# MUX_EEM_EXT.net
KiCad netlist of a schematic drawn in Altium Designer
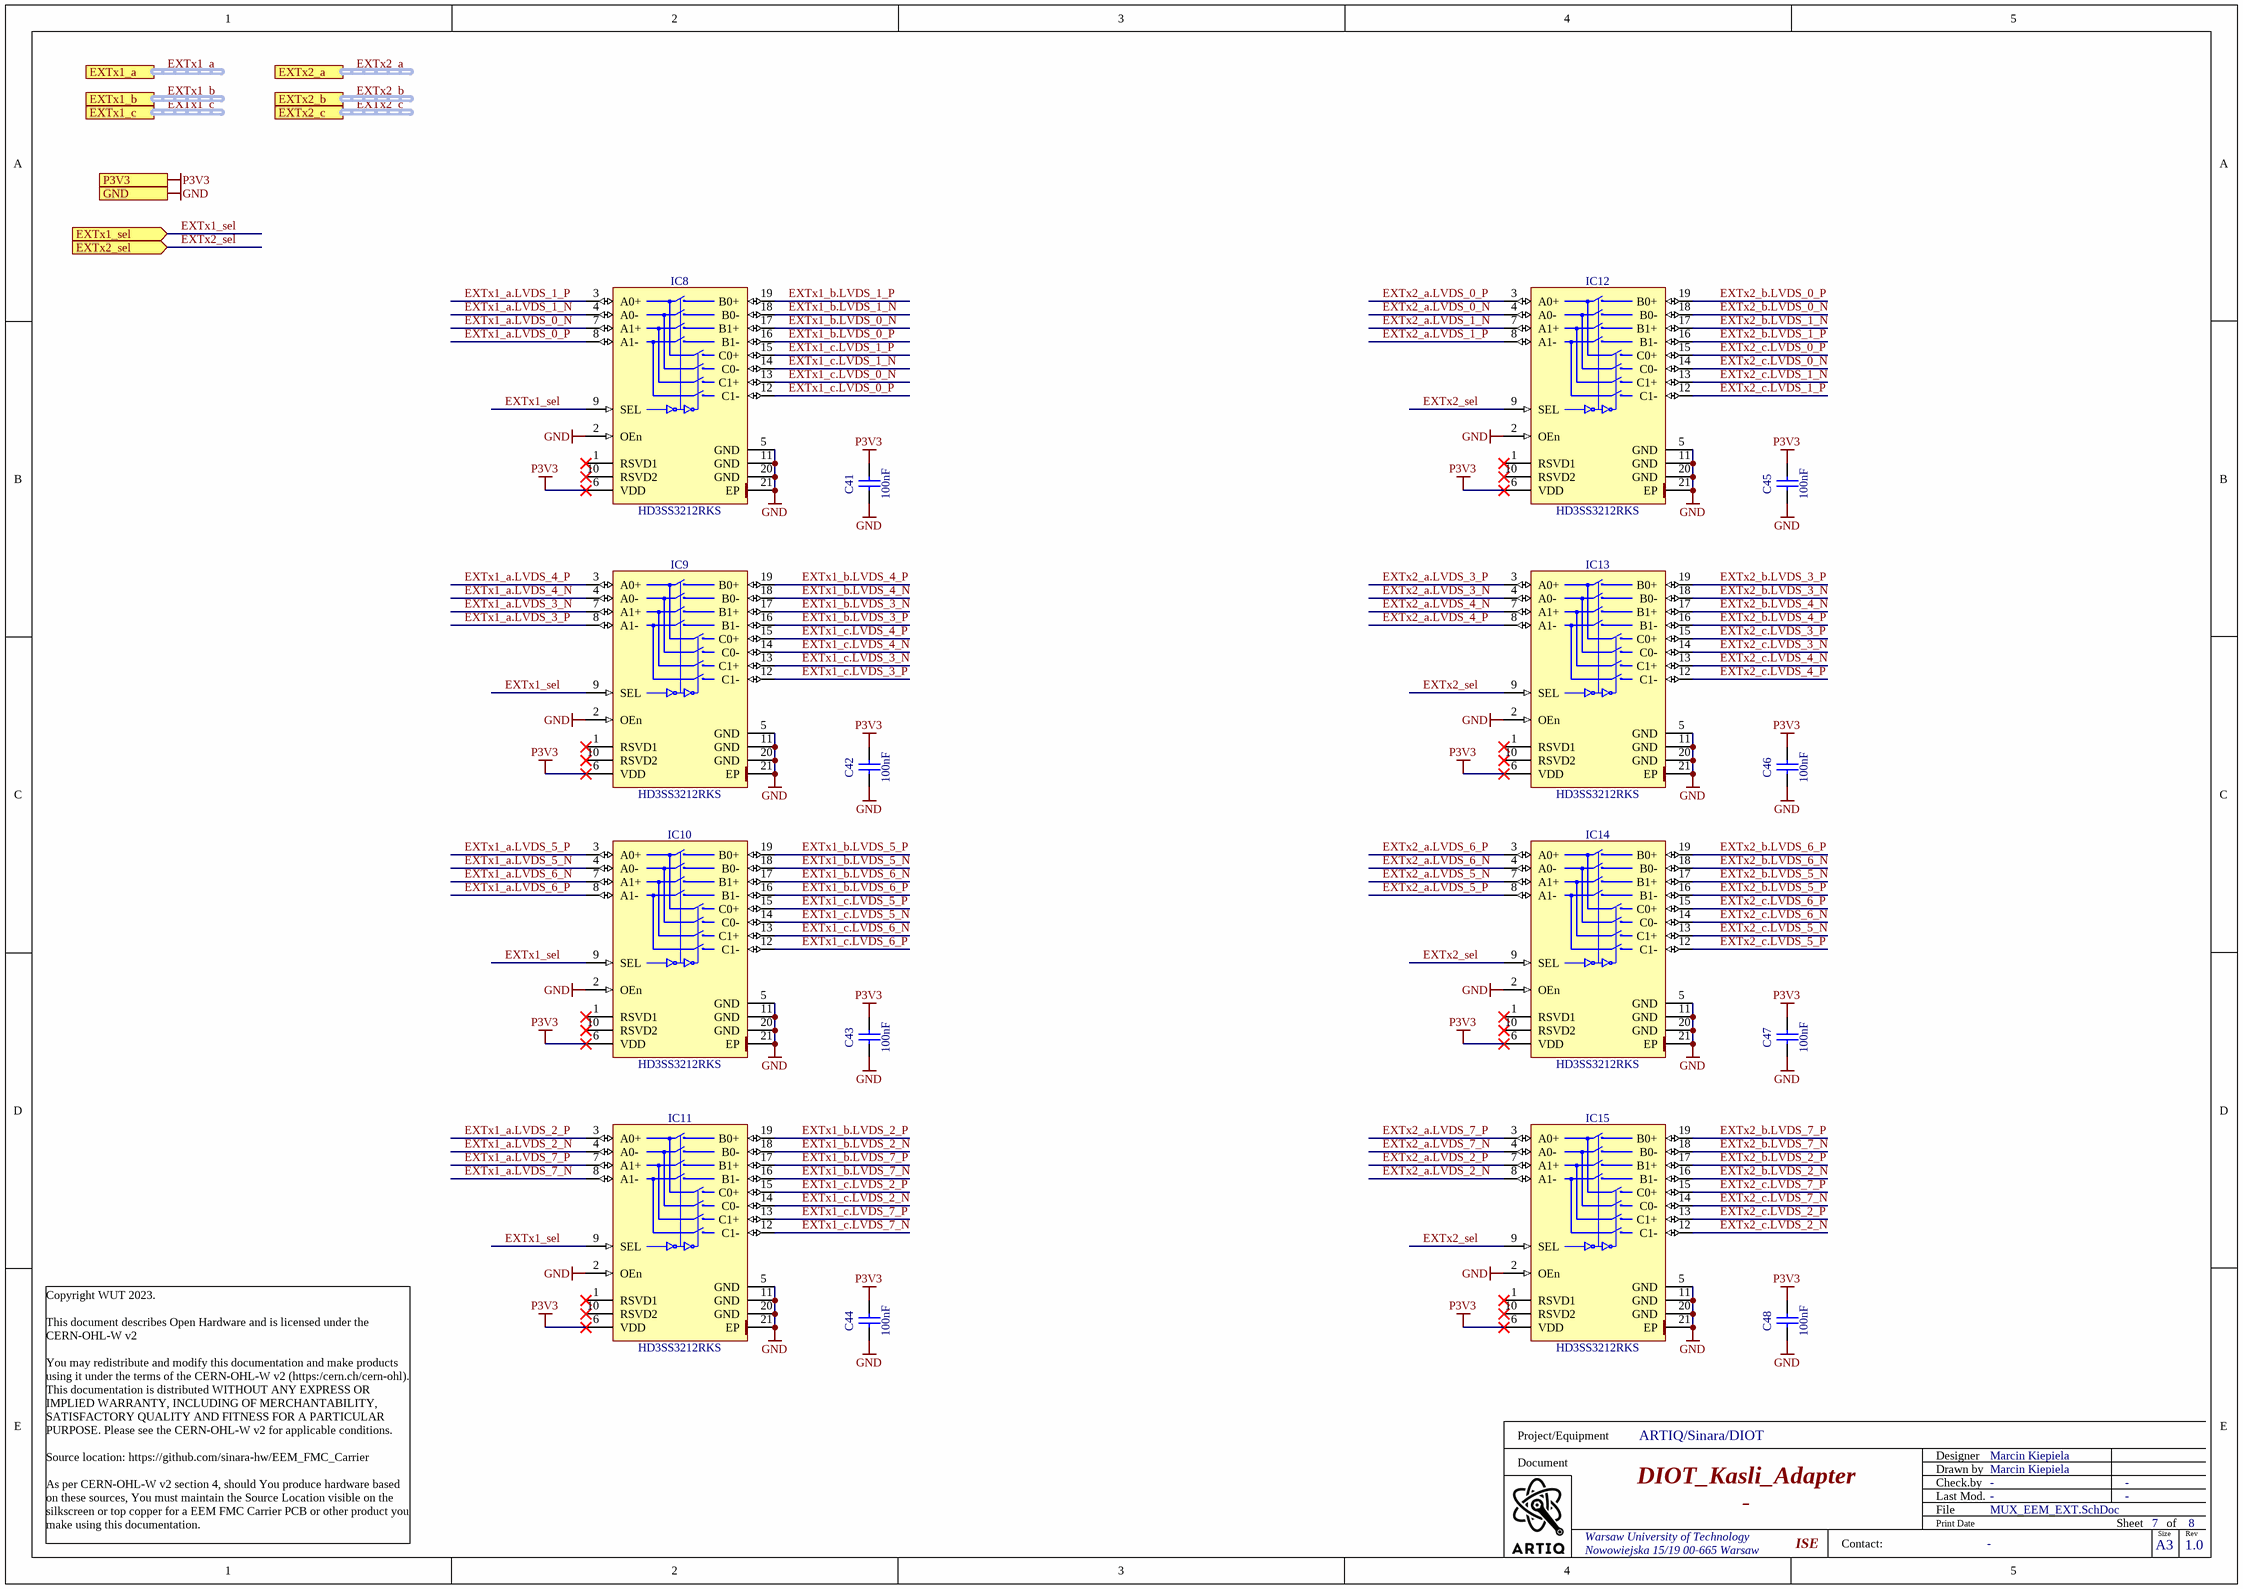
[diagram p0: MUX_EEM_EXT.SchDoc]

(export (version "E")
  (design (tool "Eeschema 10.0.6"))
  (components
    (comp (ref "C41")
      (value "100nF")
      (footprint "CAPC1005X55N")
      (description "Non-polarised capacitor")
      (fields
        (field (name "PART NUMBER") "CC0402_100NF_16V_10%_X7R")
        (field (name "VOLTAGE") "16V")
        (field (name "AUTHOR") "CERN DEM JLC")
      )
      (libsource (lib "Capacitors") (part "Capacitor - non polarized"))
    )
    (comp (ref "C42")
      (value "100nF")
      (footprint "CAPC1005X55N")
      (description "Non-polarised capacitor")
      (fields
        (field (name "PART NUMBER") "CC0402_100NF_16V_10%_X7R")
        (field (name "VOLTAGE") "16V")
        (field (name "AUTHOR") "CERN DEM JLC")
      )
      (libsource (lib "Capacitors") (part "Capacitor - non polarized"))
    )
    (comp (ref "C43")
      (value "100nF")
      (footprint "CAPC1005X55N")
      (description "Non-polarised capacitor")
      (fields
        (field (name "PART NUMBER") "CC0402_100NF_16V_10%_X7R")
        (field (name "VOLTAGE") "16V")
        (field (name "AUTHOR") "CERN DEM JLC")
      )
      (libsource (lib "Capacitors") (part "Capacitor - non polarized"))
    )
    (comp (ref "C44")
      (value "100nF")
      (footprint "CAPC1005X55N")
      (description "Non-polarised capacitor")
      (fields
        (field (name "PART NUMBER") "CC0402_100NF_16V_10%_X7R")
        (field (name "VOLTAGE") "16V")
        (field (name "AUTHOR") "CERN DEM JLC")
      )
      (libsource (lib "Capacitors") (part "Capacitor - non polarized"))
    )
    (comp (ref "C45")
      (value "100nF")
      (footprint "CAPC1005X55N")
      (description "Non-polarised capacitor")
      (fields
        (field (name "PART NUMBER") "CC0402_100NF_16V_10%_X7R")
        (field (name "VOLTAGE") "16V")
        (field (name "AUTHOR") "CERN DEM JLC")
      )
      (libsource (lib "Capacitors") (part "Capacitor - non polarized"))
    )
    (comp (ref "C46")
      (value "100nF")
      (footprint "CAPC1005X55N")
      (description "Non-polarised capacitor")
      (fields
        (field (name "PART NUMBER") "CC0402_100NF_16V_10%_X7R")
        (field (name "VOLTAGE") "16V")
        (field (name "AUTHOR") "CERN DEM JLC")
      )
      (libsource (lib "Capacitors") (part "Capacitor - non polarized"))
    )
    (comp (ref "C47")
      (value "100nF")
      (footprint "CAPC1005X55N")
      (description "Non-polarised capacitor")
      (fields
        (field (name "PART NUMBER") "CC0402_100NF_16V_10%_X7R")
        (field (name "VOLTAGE") "16V")
        (field (name "AUTHOR") "CERN DEM JLC")
      )
      (libsource (lib "Capacitors") (part "Capacitor - non polarized"))
    )
    (comp (ref "C48")
      (value "100nF")
      (footprint "CAPC1005X55N")
      (description "Non-polarised capacitor")
      (fields
        (field (name "PART NUMBER") "CC0402_100NF_16V_10%_X7R")
        (field (name "VOLTAGE") "16V")
        (field (name "AUTHOR") "CERN DEM JLC")
      )
      (libsource (lib "Capacitors") (part "Capacitor - non polarized"))
    )
    (comp (ref "IC8")
      (value "HD3SS3212RKS")
      (footprint "TEXAS_RKS0020A")
      (description "Two-Channel Differential 2:1/1:2 USB3.1 Mux/Demux")
      (fields (field (name "MANUFACTURER") "TEXAS INSTRUMENTS") (field (name "AUTHOR") "CERN DEM BC"))
      (libsource (lib "ICs And Semiconductors") (part "HD3SS3212RKS"))
    )
    (comp (ref "IC9")
      (value "HD3SS3212RKS")
      (footprint "TEXAS_RKS0020A")
      (description "Two-Channel Differential 2:1/1:2 USB3.1 Mux/Demux")
      (fields (field (name "MANUFACTURER") "TEXAS INSTRUMENTS") (field (name "AUTHOR") "CERN DEM BC"))
      (libsource (lib "ICs And Semiconductors") (part "HD3SS3212RKS"))
    )
    (comp (ref "IC10")
      (value "HD3SS3212RKS")
      (footprint "TEXAS_RKS0020A")
      (description "Two-Channel Differential 2:1/1:2 USB3.1 Mux/Demux")
      (fields (field (name "MANUFACTURER") "TEXAS INSTRUMENTS") (field (name "AUTHOR") "CERN DEM BC"))
      (libsource (lib "ICs And Semiconductors") (part "HD3SS3212RKS"))
    )
    (comp (ref "IC11")
      (value "HD3SS3212RKS")
      (footprint "TEXAS_RKS0020A")
      (description "Two-Channel Differential 2:1/1:2 USB3.1 Mux/Demux")
      (fields (field (name "MANUFACTURER") "TEXAS INSTRUMENTS") (field (name "AUTHOR") "CERN DEM BC"))
      (libsource (lib "ICs And Semiconductors") (part "HD3SS3212RKS"))
    )
    (comp (ref "IC12")
      (value "HD3SS3212RKS")
      (footprint "TEXAS_RKS0020A")
      (description "Two-Channel Differential 2:1/1:2 USB3.1 Mux/Demux")
      (fields (field (name "MANUFACTURER") "TEXAS INSTRUMENTS") (field (name "AUTHOR") "CERN DEM BC"))
      (libsource (lib "ICs And Semiconductors") (part "HD3SS3212RKS"))
    )
    (comp (ref "IC13")
      (value "HD3SS3212RKS")
      (footprint "TEXAS_RKS0020A")
      (description "Two-Channel Differential 2:1/1:2 USB3.1 Mux/Demux")
      (fields (field (name "MANUFACTURER") "TEXAS INSTRUMENTS") (field (name "AUTHOR") "CERN DEM BC"))
      (libsource (lib "ICs And Semiconductors") (part "HD3SS3212RKS"))
    )
    (comp (ref "IC14")
      (value "HD3SS3212RKS")
      (footprint "TEXAS_RKS0020A")
      (description "Two-Channel Differential 2:1/1:2 USB3.1 Mux/Demux")
      (fields (field (name "MANUFACTURER") "TEXAS INSTRUMENTS") (field (name "AUTHOR") "CERN DEM BC"))
      (libsource (lib "ICs And Semiconductors") (part "HD3SS3212RKS"))
    )
    (comp (ref "IC15")
      (value "HD3SS3212RKS")
      (footprint "TEXAS_RKS0020A")
      (description "Two-Channel Differential 2:1/1:2 USB3.1 Mux/Demux")
      (fields (field (name "MANUFACTURER") "TEXAS INSTRUMENTS") (field (name "AUTHOR") "CERN DEM BC"))
      (libsource (lib "ICs And Semiconductors") (part "HD3SS3212RKS"))
    )
  )
  (nets
    (net (code "7") (name "/EXTx1_a.LVDS_0_N") (class "Default")
      (node (ref "IC8") (pin "7") (pinfunction "A1+_7") (pintype "bidirectional"))
    )
    (net (code "8") (name "/EXTx1_a.LVDS_0_P") (class "Default")
      (node (ref "IC8") (pin "8") (pinfunction "A1-_8") (pintype "bidirectional"))
    )
    (net (code "9") (name "/EXTx1_a.LVDS_1_N") (class "Default")
      (node (ref "IC8") (pin "4") (pinfunction "A0-_4") (pintype "bidirectional"))
    )
    (net (code "10") (name "/EXTx1_a.LVDS_1_P") (class "Default")
      (node (ref "IC8") (pin "3") (pinfunction "A0+_3") (pintype "bidirectional"))
    )
    (net (code "11") (name "/EXTx1_a.LVDS_2_N") (class "Default")
      (node (ref "IC11") (pin "4") (pinfunction "A0-_4") (pintype "bidirectional"))
    )
    (net (code "12") (name "/EXTx1_a.LVDS_2_P") (class "Default")
      (node (ref "IC11") (pin "3") (pinfunction "A0+_3") (pintype "bidirectional"))
    )
    (net (code "13") (name "/EXTx1_a.LVDS_3_N") (class "Default")
      (node (ref "IC9") (pin "7") (pinfunction "A1+_7") (pintype "bidirectional"))
    )
    (net (code "14") (name "/EXTx1_a.LVDS_3_P") (class "Default")
      (node (ref "IC9") (pin "8") (pinfunction "A1-_8") (pintype "bidirectional"))
    )
    (net (code "15") (name "/EXTx1_a.LVDS_4_N") (class "Default")
      (node (ref "IC9") (pin "4") (pinfunction "A0-_4") (pintype "bidirectional"))
    )
    (net (code "16") (name "/EXTx1_a.LVDS_4_P") (class "Default")
      (node (ref "IC9") (pin "3") (pinfunction "A0+_3") (pintype "bidirectional"))
    )
    (net (code "17") (name "/EXTx1_a.LVDS_5_N") (class "Default")
      (node (ref "IC10") (pin "4") (pinfunction "A0-_4") (pintype "bidirectional"))
    )
    (net (code "18") (name "/EXTx1_a.LVDS_5_P") (class "Default")
      (node (ref "IC10") (pin "3") (pinfunction "A0+_3") (pintype "bidirectional"))
    )
    (net (code "19") (name "/EXTx1_a.LVDS_6_N") (class "Default")
      (node (ref "IC10") (pin "7") (pinfunction "A1+_7") (pintype "bidirectional"))
    )
    (net (code "20") (name "/EXTx1_a.LVDS_6_P") (class "Default")
      (node (ref "IC10") (pin "8") (pinfunction "A1-_8") (pintype "bidirectional"))
    )
    (net (code "21") (name "/EXTx1_a.LVDS_7_N") (class "Default")
      (node (ref "IC11") (pin "8") (pinfunction "A1-_8") (pintype "bidirectional"))
    )
    (net (code "22") (name "/EXTx1_a.LVDS_7_P") (class "Default")
      (node (ref "IC11") (pin "7") (pinfunction "A1+_7") (pintype "bidirectional"))
    )
    (net (code "23") (name "/EXTx1_b.LVDS_0_N") (class "Default")
      (node (ref "IC8") (pin "17") (pinfunction "B1+_17") (pintype "bidirectional"))
    )
    (net (code "24") (name "/EXTx1_b.LVDS_0_P") (class "Default")
      (node (ref "IC8") (pin "16") (pinfunction "B1-_16") (pintype "bidirectional"))
    )
    (net (code "25") (name "/EXTx1_b.LVDS_1_N") (class "Default")
      (node (ref "IC8") (pin "18") (pinfunction "B0-_18") (pintype "bidirectional"))
    )
    (net (code "26") (name "/EXTx1_b.LVDS_1_P") (class "Default")
      (node (ref "IC8") (pin "19") (pinfunction "B0+_19") (pintype "bidirectional"))
    )
    (net (code "27") (name "/EXTx1_b.LVDS_2_N") (class "Default")
      (node (ref "IC11") (pin "18") (pinfunction "B0-_18") (pintype "bidirectional"))
    )
    (net (code "28") (name "/EXTx1_b.LVDS_2_P") (class "Default")
      (node (ref "IC11") (pin "19") (pinfunction "B0+_19") (pintype "bidirectional"))
    )
    (net (code "29") (name "/EXTx1_b.LVDS_3_N") (class "Default")
      (node (ref "IC9") (pin "17") (pinfunction "B1+_17") (pintype "bidirectional"))
    )
    (net (code "30") (name "/EXTx1_b.LVDS_3_P") (class "Default")
      (node (ref "IC9") (pin "16") (pinfunction "B1-_16") (pintype "bidirectional"))
    )
    (net (code "31") (name "/EXTx1_b.LVDS_4_N") (class "Default")
      (node (ref "IC9") (pin "18") (pinfunction "B0-_18") (pintype "bidirectional"))
    )
    (net (code "32") (name "/EXTx1_b.LVDS_4_P") (class "Default")
      (node (ref "IC9") (pin "19") (pinfunction "B0+_19") (pintype "bidirectional"))
    )
    (net (code "33") (name "/EXTx1_b.LVDS_5_N") (class "Default")
      (node (ref "IC10") (pin "18") (pinfunction "B0-_18") (pintype "bidirectional"))
    )
    (net (code "34") (name "/EXTx1_b.LVDS_5_P") (class "Default")
      (node (ref "IC10") (pin "19") (pinfunction "B0+_19") (pintype "bidirectional"))
    )
    (net (code "35") (name "/EXTx1_b.LVDS_6_N") (class "Default")
      (node (ref "IC10") (pin "17") (pinfunction "B1+_17") (pintype "bidirectional"))
    )
    (net (code "36") (name "/EXTx1_b.LVDS_6_P") (class "Default")
      (node (ref "IC10") (pin "16") (pinfunction "B1-_16") (pintype "bidirectional"))
    )
    (net (code "37") (name "/EXTx1_b.LVDS_7_N") (class "Default")
      (node (ref "IC11") (pin "16") (pinfunction "B1-_16") (pintype "bidirectional"))
    )
    (net (code "38") (name "/EXTx1_b.LVDS_7_P") (class "Default")
      (node (ref "IC11") (pin "17") (pinfunction "B1+_17") (pintype "bidirectional"))
    )
    (net (code "39") (name "/EXTx1_c.LVDS_0_N") (class "Default")
      (node (ref "IC8") (pin "13") (pinfunction "C1+_13") (pintype "bidirectional"))
    )
    (net (code "40") (name "/EXTx1_c.LVDS_0_P") (class "Default")
      (node (ref "IC8") (pin "12") (pinfunction "C1-_12") (pintype "bidirectional"))
    )
    (net (code "41") (name "/EXTx1_c.LVDS_1_N") (class "Default")
      (node (ref "IC8") (pin "14") (pinfunction "C0-_14") (pintype "bidirectional"))
    )
    (net (code "42") (name "/EXTx1_c.LVDS_1_P") (class "Default")
      (node (ref "IC8") (pin "15") (pinfunction "C0+_15") (pintype "bidirectional"))
    )
    (net (code "43") (name "/EXTx1_c.LVDS_2_N") (class "Default")
      (node (ref "IC11") (pin "14") (pinfunction "C0-_14") (pintype "bidirectional"))
    )
    (net (code "44") (name "/EXTx1_c.LVDS_2_P") (class "Default")
      (node (ref "IC11") (pin "15") (pinfunction "C0+_15") (pintype "bidirectional"))
    )
    (net (code "45") (name "/EXTx1_c.LVDS_3_N") (class "Default")
      (node (ref "IC9") (pin "13") (pinfunction "C1+_13") (pintype "bidirectional"))
    )
    (net (code "46") (name "/EXTx1_c.LVDS_3_P") (class "Default")
      (node (ref "IC9") (pin "12") (pinfunction "C1-_12") (pintype "bidirectional"))
    )
    (net (code "47") (name "/EXTx1_c.LVDS_4_N") (class "Default")
      (node (ref "IC9") (pin "14") (pinfunction "C0-_14") (pintype "bidirectional"))
    )
    (net (code "48") (name "/EXTx1_c.LVDS_4_P") (class "Default")
      (node (ref "IC9") (pin "15") (pinfunction "C0+_15") (pintype "bidirectional"))
    )
    (net (code "49") (name "/EXTx1_c.LVDS_5_N") (class "Default")
      (node (ref "IC10") (pin "14") (pinfunction "C0-_14") (pintype "bidirectional"))
    )
    (net (code "50") (name "/EXTx1_c.LVDS_5_P") (class "Default")
      (node (ref "IC10") (pin "15") (pinfunction "C0+_15") (pintype "bidirectional"))
    )
    (net (code "51") (name "/EXTx1_c.LVDS_6_N") (class "Default")
      (node (ref "IC10") (pin "13") (pinfunction "C1+_13") (pintype "bidirectional"))
    )
    (net (code "52") (name "/EXTx1_c.LVDS_6_P") (class "Default")
      (node (ref "IC10") (pin "12") (pinfunction "C1-_12") (pintype "bidirectional"))
    )
    (net (code "53") (name "/EXTx1_c.LVDS_7_N") (class "Default")
      (node (ref "IC11") (pin "12") (pinfunction "C1-_12") (pintype "bidirectional"))
    )
    (net (code "54") (name "/EXTx1_c.LVDS_7_P") (class "Default")
      (node (ref "IC11") (pin "13") (pinfunction "C1+_13") (pintype "bidirectional"))
    )
    (net (code "55") (name "/EXTx1_sel") (class "Default")
      (node (ref "IC10") (pin "9") (pinfunction "SEL_9") (pintype "input"))
      (node (ref "IC11") (pin "9") (pinfunction "SEL_9") (pintype "input"))
      (node (ref "IC8") (pin "9") (pinfunction "SEL_9") (pintype "input"))
      (node (ref "IC9") (pin "9") (pinfunction "SEL_9") (pintype "input"))
    )
    (net (code "56") (name "/EXTx2_a.LVDS_0_N") (class "Default")
      (node (ref "IC12") (pin "4") (pinfunction "A0-_4") (pintype "bidirectional"))
    )
    (net (code "57") (name "/EXTx2_a.LVDS_0_P") (class "Default")
      (node (ref "IC12") (pin "3") (pinfunction "A0+_3") (pintype "bidirectional"))
    )
    (net (code "58") (name "/EXTx2_a.LVDS_1_N") (class "Default")
      (node (ref "IC12") (pin "7") (pinfunction "A1+_7") (pintype "bidirectional"))
    )
    (net (code "59") (name "/EXTx2_a.LVDS_1_P") (class "Default")
      (node (ref "IC12") (pin "8") (pinfunction "A1-_8") (pintype "bidirectional"))
    )
    (net (code "60") (name "/EXTx2_a.LVDS_2_N") (class "Default")
      (node (ref "IC15") (pin "8") (pinfunction "A1-_8") (pintype "bidirectional"))
    )
    (net (code "61") (name "/EXTx2_a.LVDS_2_P") (class "Default")
      (node (ref "IC15") (pin "7") (pinfunction "A1+_7") (pintype "bidirectional"))
    )
    (net (code "62") (name "/EXTx2_a.LVDS_3_N") (class "Default")
      (node (ref "IC13") (pin "4") (pinfunction "A0-_4") (pintype "bidirectional"))
    )
    (net (code "63") (name "/EXTx2_a.LVDS_3_P") (class "Default")
      (node (ref "IC13") (pin "3") (pinfunction "A0+_3") (pintype "bidirectional"))
    )
    (net (code "64") (name "/EXTx2_a.LVDS_4_N") (class "Default")
      (node (ref "IC13") (pin "7") (pinfunction "A1+_7") (pintype "bidirectional"))
    )
    (net (code "65") (name "/EXTx2_a.LVDS_4_P") (class "Default")
      (node (ref "IC13") (pin "8") (pinfunction "A1-_8") (pintype "bidirectional"))
    )
    (net (code "66") (name "/EXTx2_a.LVDS_5_N") (class "Default")
      (node (ref "IC14") (pin "7") (pinfunction "A1+_7") (pintype "bidirectional"))
    )
    (net (code "67") (name "/EXTx2_a.LVDS_5_P") (class "Default")
      (node (ref "IC14") (pin "8") (pinfunction "A1-_8") (pintype "bidirectional"))
    )
    (net (code "68") (name "/EXTx2_a.LVDS_6_N") (class "Default")
      (node (ref "IC14") (pin "4") (pinfunction "A0-_4") (pintype "bidirectional"))
    )
    (net (code "69") (name "/EXTx2_a.LVDS_6_P") (class "Default")
      (node (ref "IC14") (pin "3") (pinfunction "A0+_3") (pintype "bidirectional"))
    )
    (net (code "70") (name "/EXTx2_a.LVDS_7_N") (class "Default")
      (node (ref "IC15") (pin "4") (pinfunction "A0-_4") (pintype "bidirectional"))
    )
    (net (code "71") (name "/EXTx2_a.LVDS_7_P") (class "Default")
      (node (ref "IC15") (pin "3") (pinfunction "A0+_3") (pintype "bidirectional"))
    )
    (net (code "72") (name "/EXTx2_b.LVDS_0_N") (class "Default")
      (node (ref "IC12") (pin "18") (pinfunction "B0-_18") (pintype "bidirectional"))
    )
    (net (code "73") (name "/EXTx2_b.LVDS_0_P") (class "Default")
      (node (ref "IC12") (pin "19") (pinfunction "B0+_19") (pintype "bidirectional"))
    )
    (net (code "74") (name "/EXTx2_b.LVDS_1_N") (class "Default")
      (node (ref "IC12") (pin "17") (pinfunction "B1+_17") (pintype "bidirectional"))
    )
    (net (code "75") (name "/EXTx2_b.LVDS_1_P") (class "Default")
      (node (ref "IC12") (pin "16") (pinfunction "B1-_16") (pintype "bidirectional"))
    )
    (net (code "76") (name "/EXTx2_b.LVDS_2_N") (class "Default")
      (node (ref "IC15") (pin "16") (pinfunction "B1-_16") (pintype "bidirectional"))
    )
    (net (code "77") (name "/EXTx2_b.LVDS_2_P") (class "Default")
      (node (ref "IC15") (pin "17") (pinfunction "B1+_17") (pintype "bidirectional"))
    )
    (net (code "78") (name "/EXTx2_b.LVDS_3_N") (class "Default")
      (node (ref "IC13") (pin "18") (pinfunction "B0-_18") (pintype "bidirectional"))
    )
    (net (code "79") (name "/EXTx2_b.LVDS_3_P") (class "Default")
      (node (ref "IC13") (pin "19") (pinfunction "B0+_19") (pintype "bidirectional"))
    )
    (net (code "80") (name "/EXTx2_b.LVDS_4_N") (class "Default")
      (node (ref "IC13") (pin "17") (pinfunction "B1+_17") (pintype "bidirectional"))
    )
    (net (code "81") (name "/EXTx2_b.LVDS_4_P") (class "Default")
      (node (ref "IC13") (pin "16") (pinfunction "B1-_16") (pintype "bidirectional"))
    )
    (net (code "82") (name "/EXTx2_b.LVDS_5_N") (class "Default")
      (node (ref "IC14") (pin "17") (pinfunction "B1+_17") (pintype "bidirectional"))
    )
    (net (code "83") (name "/EXTx2_b.LVDS_5_P") (class "Default")
      (node (ref "IC14") (pin "16") (pinfunction "B1-_16") (pintype "bidirectional"))
    )
    (net (code "84") (name "/EXTx2_b.LVDS_6_N") (class "Default")
      (node (ref "IC14") (pin "18") (pinfunction "B0-_18") (pintype "bidirectional"))
    )
    (net (code "85") (name "/EXTx2_b.LVDS_6_P") (class "Default")
      (node (ref "IC14") (pin "19") (pinfunction "B0+_19") (pintype "bidirectional"))
    )
    (net (code "86") (name "/EXTx2_b.LVDS_7_N") (class "Default")
      (node (ref "IC15") (pin "18") (pinfunction "B0-_18") (pintype "bidirectional"))
    )
    (net (code "87") (name "/EXTx2_b.LVDS_7_P") (class "Default")
      (node (ref "IC15") (pin "19") (pinfunction "B0+_19") (pintype "bidirectional"))
    )
    (net (code "88") (name "/EXTx2_c.LVDS_0_N") (class "Default")
      (node (ref "IC12") (pin "14") (pinfunction "C0-_14") (pintype "bidirectional"))
    )
    (net (code "89") (name "/EXTx2_c.LVDS_0_P") (class "Default")
      (node (ref "IC12") (pin "15") (pinfunction "C0+_15") (pintype "bidirectional"))
    )
    (net (code "90") (name "/EXTx2_c.LVDS_1_N") (class "Default")
      (node (ref "IC12") (pin "13") (pinfunction "C1+_13") (pintype "bidirectional"))
    )
    (net (code "91") (name "/EXTx2_c.LVDS_1_P") (class "Default")
      (node (ref "IC12") (pin "12") (pinfunction "C1-_12") (pintype "bidirectional"))
    )
    (net (code "92") (name "/EXTx2_c.LVDS_2_N") (class "Default")
      (node (ref "IC15") (pin "12") (pinfunction "C1-_12") (pintype "bidirectional"))
    )
    (net (code "93") (name "/EXTx2_c.LVDS_2_P") (class "Default")
      (node (ref "IC15") (pin "13") (pinfunction "C1+_13") (pintype "bidirectional"))
    )
    (net (code "94") (name "/EXTx2_c.LVDS_3_N") (class "Default")
      (node (ref "IC13") (pin "14") (pinfunction "C0-_14") (pintype "bidirectional"))
    )
    (net (code "95") (name "/EXTx2_c.LVDS_3_P") (class "Default")
      (node (ref "IC13") (pin "15") (pinfunction "C0+_15") (pintype "bidirectional"))
    )
    (net (code "96") (name "/EXTx2_c.LVDS_4_N") (class "Default")
      (node (ref "IC13") (pin "13") (pinfunction "C1+_13") (pintype "bidirectional"))
    )
    (net (code "97") (name "/EXTx2_c.LVDS_4_P") (class "Default")
      (node (ref "IC13") (pin "12") (pinfunction "C1-_12") (pintype "bidirectional"))
    )
    (net (code "98") (name "/EXTx2_c.LVDS_5_N") (class "Default")
      (node (ref "IC14") (pin "13") (pinfunction "C1+_13") (pintype "bidirectional"))
    )
    (net (code "99") (name "/EXTx2_c.LVDS_5_P") (class "Default")
      (node (ref "IC14") (pin "12") (pinfunction "C1-_12") (pintype "bidirectional"))
    )
    (net (code "100") (name "/EXTx2_c.LVDS_6_N") (class "Default")
      (node (ref "IC14") (pin "14") (pinfunction "C0-_14") (pintype "bidirectional"))
    )
    (net (code "101") (name "/EXTx2_c.LVDS_6_P") (class "Default")
      (node (ref "IC14") (pin "15") (pinfunction "C0+_15") (pintype "bidirectional"))
    )
    (net (code "102") (name "/EXTx2_c.LVDS_7_N") (class "Default")
      (node (ref "IC15") (pin "14") (pinfunction "C0-_14") (pintype "bidirectional"))
    )
    (net (code "103") (name "/EXTx2_c.LVDS_7_P") (class "Default")
      (node (ref "IC15") (pin "15") (pinfunction "C0+_15") (pintype "bidirectional"))
    )
    (net (code "104") (name "/EXTx2_sel") (class "Default")
      (node (ref "IC12") (pin "9") (pinfunction "SEL_9") (pintype "input"))
      (node (ref "IC13") (pin "9") (pinfunction "SEL_9") (pintype "input"))
      (node (ref "IC14") (pin "9") (pinfunction "SEL_9") (pintype "input"))
      (node (ref "IC15") (pin "9") (pinfunction "SEL_9") (pintype "input"))
    )
    (net (code "111") (name "GND") (class "Default")
      (node (ref "C41") (pin "1") (pinfunction "1_1") (pintype "passive"))
      (node (ref "C42") (pin "1") (pinfunction "1_1") (pintype "passive"))
      (node (ref "C43") (pin "1") (pinfunction "1_1") (pintype "passive"))
      (node (ref "C44") (pin "1") (pinfunction "1_1") (pintype "passive"))
      (node (ref "C45") (pin "1") (pinfunction "1_1") (pintype "passive"))
      (node (ref "C46") (pin "1") (pinfunction "1_1") (pintype "passive"))
      (node (ref "C47") (pin "1") (pinfunction "1_1") (pintype "passive"))
      (node (ref "C48") (pin "1") (pinfunction "1_1") (pintype "passive"))
      (node (ref "IC10") (pin "11") (pinfunction "GND_11") (pintype "power_in"))
      (node (ref "IC10") (pin "2") (pinfunction "OEn_2") (pintype "input"))
      (node (ref "IC10") (pin "20") (pinfunction "GND_20") (pintype "power_in"))
      (node (ref "IC10") (pin "21") (pinfunction "EP_21") (pintype "power_in"))
      (node (ref "IC10") (pin "5") (pinfunction "GND_5") (pintype "power_in"))
      (node (ref "IC11") (pin "11") (pinfunction "GND_11") (pintype "power_in"))
      (node (ref "IC11") (pin "2") (pinfunction "OEn_2") (pintype "input"))
      (node (ref "IC11") (pin "20") (pinfunction "GND_20") (pintype "power_in"))
      (node (ref "IC11") (pin "21") (pinfunction "EP_21") (pintype "power_in"))
      (node (ref "IC11") (pin "5") (pinfunction "GND_5") (pintype "power_in"))
      (node (ref "IC12") (pin "11") (pinfunction "GND_11") (pintype "power_in"))
      (node (ref "IC12") (pin "2") (pinfunction "OEn_2") (pintype "input"))
      (node (ref "IC12") (pin "20") (pinfunction "GND_20") (pintype "power_in"))
      (node (ref "IC12") (pin "21") (pinfunction "EP_21") (pintype "power_in"))
      (node (ref "IC12") (pin "5") (pinfunction "GND_5") (pintype "power_in"))
      (node (ref "IC13") (pin "11") (pinfunction "GND_11") (pintype "power_in"))
      (node (ref "IC13") (pin "2") (pinfunction "OEn_2") (pintype "input"))
      (node (ref "IC13") (pin "20") (pinfunction "GND_20") (pintype "power_in"))
      (node (ref "IC13") (pin "21") (pinfunction "EP_21") (pintype "power_in"))
      (node (ref "IC13") (pin "5") (pinfunction "GND_5") (pintype "power_in"))
      (node (ref "IC14") (pin "11") (pinfunction "GND_11") (pintype "power_in"))
      (node (ref "IC14") (pin "2") (pinfunction "OEn_2") (pintype "input"))
      (node (ref "IC14") (pin "20") (pinfunction "GND_20") (pintype "power_in"))
      (node (ref "IC14") (pin "21") (pinfunction "EP_21") (pintype "power_in"))
      (node (ref "IC14") (pin "5") (pinfunction "GND_5") (pintype "power_in"))
      (node (ref "IC15") (pin "11") (pinfunction "GND_11") (pintype "power_in"))
      (node (ref "IC15") (pin "2") (pinfunction "OEn_2") (pintype "input"))
      (node (ref "IC15") (pin "20") (pinfunction "GND_20") (pintype "power_in"))
      (node (ref "IC15") (pin "21") (pinfunction "EP_21") (pintype "power_in"))
      (node (ref "IC15") (pin "5") (pinfunction "GND_5") (pintype "power_in"))
      (node (ref "IC8") (pin "11") (pinfunction "GND_11") (pintype "power_in"))
      (node (ref "IC8") (pin "2") (pinfunction "OEn_2") (pintype "input"))
      (node (ref "IC8") (pin "20") (pinfunction "GND_20") (pintype "power_in"))
      (node (ref "IC8") (pin "21") (pinfunction "EP_21") (pintype "power_in"))
      (node (ref "IC8") (pin "5") (pinfunction "GND_5") (pintype "power_in"))
      (node (ref "IC9") (pin "11") (pinfunction "GND_11") (pintype "power_in"))
      (node (ref "IC9") (pin "2") (pinfunction "OEn_2") (pintype "input"))
      (node (ref "IC9") (pin "20") (pinfunction "GND_20") (pintype "power_in"))
      (node (ref "IC9") (pin "21") (pinfunction "EP_21") (pintype "power_in"))
      (node (ref "IC9") (pin "5") (pinfunction "GND_5") (pintype "power_in"))
    )
    (net (code "112") (name "P3V3") (class "Default")
      (node (ref "C41") (pin "2") (pinfunction "2_2") (pintype "passive"))
      (node (ref "C42") (pin "2") (pinfunction "2_2") (pintype "passive"))
      (node (ref "C43") (pin "2") (pinfunction "2_2") (pintype "passive"))
      (node (ref "C44") (pin "2") (pinfunction "2_2") (pintype "passive"))
      (node (ref "C45") (pin "2") (pinfunction "2_2") (pintype "passive"))
      (node (ref "C46") (pin "2") (pinfunction "2_2") (pintype "passive"))
      (node (ref "C47") (pin "2") (pinfunction "2_2") (pintype "passive"))
      (node (ref "C48") (pin "2") (pinfunction "2_2") (pintype "passive"))
      (node (ref "IC10") (pin "6") (pinfunction "VDD_6") (pintype "power_in"))
      (node (ref "IC11") (pin "6") (pinfunction "VDD_6") (pintype "power_in"))
      (node (ref "IC12") (pin "6") (pinfunction "VDD_6") (pintype "power_in"))
      (node (ref "IC13") (pin "6") (pinfunction "VDD_6") (pintype "power_in"))
      (node (ref "IC14") (pin "6") (pinfunction "VDD_6") (pintype "power_in"))
      (node (ref "IC15") (pin "6") (pinfunction "VDD_6") (pintype "power_in"))
      (node (ref "IC8") (pin "6") (pinfunction "VDD_6") (pintype "power_in"))
      (node (ref "IC9") (pin "6") (pinfunction "VDD_6") (pintype "power_in"))
    )
    (net (code "113") (name "unconnected-(IC8-RSVD1-Pad1)") (class "Default")
      (node (ref "IC8") (pin "1") (pinfunction "RSVD1_1") (pintype "power_in+no_connect"))
    )
    (net (code "114") (name "unconnected-(IC8-RSVD2-Pad10)") (class "Default")
      (node (ref "IC8") (pin "10") (pinfunction "RSVD2_10") (pintype "power_in+no_connect"))
    )
    (net (code "115") (name "unconnected-(IC9-RSVD1-Pad1)") (class "Default")
      (node (ref "IC9") (pin "1") (pinfunction "RSVD1_1") (pintype "power_in+no_connect"))
    )
    (net (code "116") (name "unconnected-(IC9-RSVD2-Pad10)") (class "Default")
      (node (ref "IC9") (pin "10") (pinfunction "RSVD2_10") (pintype "power_in+no_connect"))
    )
    (net (code "117") (name "unconnected-(IC10-RSVD1-Pad1)") (class "Default")
      (node (ref "IC10") (pin "1") (pinfunction "RSVD1_1") (pintype "power_in+no_connect"))
    )
    (net (code "118") (name "unconnected-(IC10-RSVD2-Pad10)") (class "Default")
      (node (ref "IC10") (pin "10") (pinfunction "RSVD2_10") (pintype "power_in+no_connect"))
    )
    (net (code "119") (name "unconnected-(IC11-RSVD1-Pad1)") (class "Default")
      (node (ref "IC11") (pin "1") (pinfunction "RSVD1_1") (pintype "power_in+no_connect"))
    )
    (net (code "120") (name "unconnected-(IC11-RSVD2-Pad10)") (class "Default")
      (node (ref "IC11") (pin "10") (pinfunction "RSVD2_10") (pintype "power_in+no_connect"))
    )
    (net (code "121") (name "unconnected-(IC12-RSVD1-Pad1)") (class "Default")
      (node (ref "IC12") (pin "1") (pinfunction "RSVD1_1") (pintype "power_in+no_connect"))
    )
    (net (code "122") (name "unconnected-(IC12-RSVD2-Pad10)") (class "Default")
      (node (ref "IC12") (pin "10") (pinfunction "RSVD2_10") (pintype "power_in+no_connect"))
    )
    (net (code "123") (name "unconnected-(IC13-RSVD1-Pad1)") (class "Default")
      (node (ref "IC13") (pin "1") (pinfunction "RSVD1_1") (pintype "power_in+no_connect"))
    )
    (net (code "124") (name "unconnected-(IC13-RSVD2-Pad10)") (class "Default")
      (node (ref "IC13") (pin "10") (pinfunction "RSVD2_10") (pintype "power_in+no_connect"))
    )
    (net (code "125") (name "unconnected-(IC14-RSVD1-Pad1)") (class "Default")
      (node (ref "IC14") (pin "1") (pinfunction "RSVD1_1") (pintype "power_in+no_connect"))
    )
    (net (code "126") (name "unconnected-(IC14-RSVD2-Pad10)") (class "Default")
      (node (ref "IC14") (pin "10") (pinfunction "RSVD2_10") (pintype "power_in+no_connect"))
    )
    (net (code "127") (name "unconnected-(IC15-RSVD1-Pad1)") (class "Default")
      (node (ref "IC15") (pin "1") (pinfunction "RSVD1_1") (pintype "power_in+no_connect"))
    )
    (net (code "128") (name "unconnected-(IC15-RSVD2-Pad10)") (class "Default")
      (node (ref "IC15") (pin "10") (pinfunction "RSVD2_10") (pintype "power_in+no_connect"))
    )
  )
)
